# node.net
KiCad netlist of a schematic drawn in Altium Designer
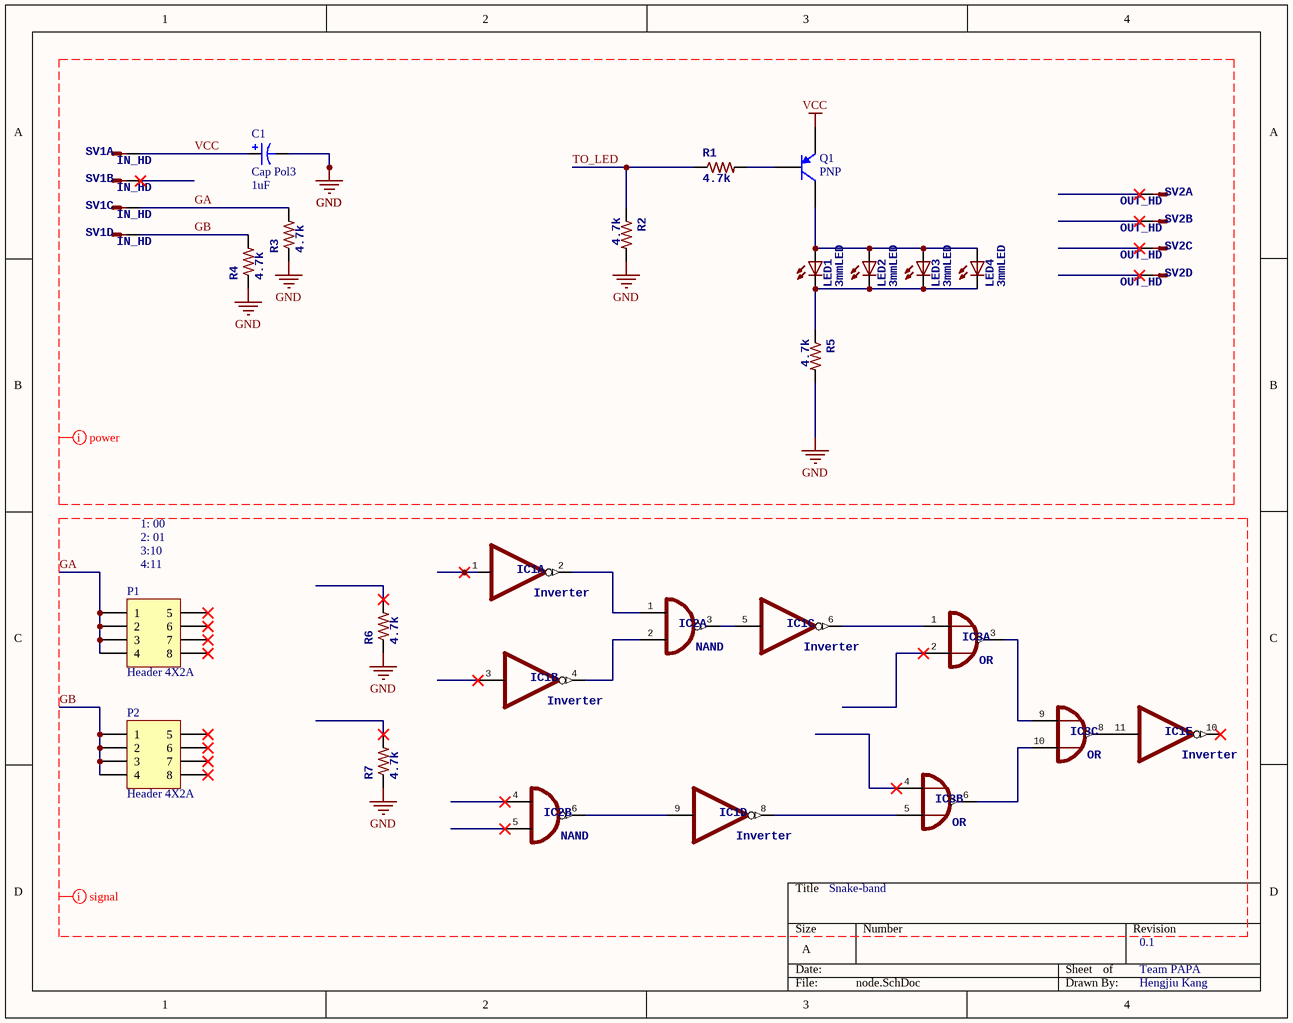
[diagram p0: node.SchDoc]

(export (version "E")
  (design (tool "Eeschema 10.0.6"))
  (components
    (comp (ref "C1")
      (value "Cap Pol3")
      (footprint "C0805")
      (description "Polarized Capacitor (Surface Mount)")
      (fields (field (name "ALTIUM_VALUE") "1uF") (field (name "PUBLISHER") "Altium Limited"))
      (libsource (lib "Miscellaneous Devices") (part "Cap Pol3"))
    )
    (comp (ref "IC1") (value "Inverter") (footprint "ssop14") (libsource (lib "74xx-eu") (part "74*04DB")))
    (comp (ref "IC2") (value "NAND") (footprint "SSOP14") (libsource (lib "74xx-eu") (part "74*00DB")))
    (comp (ref "IC3") (value "OR") (footprint "ssop14") (libsource (lib "74xx-eu") (part "74*32DB")))
    (comp (ref "LED1") (value "3mmLED") (footprint "LED3MM") (libsource (lib "adafruit") (part "LED3MM")))
    (comp (ref "LED2") (value "3mmLED") (footprint "LED3MM") (libsource (lib "adafruit") (part "LED3MM")))
    (comp (ref "LED3") (value "3mmLED") (footprint "LED3MM") (libsource (lib "adafruit") (part "LED3MM")))
    (comp (ref "LED4") (value "3mmLED") (footprint "LED3MM") (libsource (lib "adafruit") (part "LED3MM")))
    (comp (ref "P1")
      (value "Header 4X2A")
      (footprint "HDR2X4_CEN")
      (description "Header, 4-Pin, Dual row")
      (fields (field (name "PUBLISHER") "Altium Limited"))
      (libsource (lib "Miscellaneous Connectors") (part "Header 4X2A"))
    )
    (comp (ref "P2")
      (value "Header 4X2A")
      (footprint "HDR2X4_CEN")
      (description "Header, 4-Pin, Dual row")
      (fields (field (name "PUBLISHER") "Altium Limited"))
      (libsource (lib "Miscellaneous Connectors") (part "Header 4X2A"))
    )
    (comp (ref "Q1")
      (value "PNP")
      (footprint "SOT-23B_N")
      (description "PNP Bipolar Transistor")
      (fields (field (name "PUBLISHER") "Altium Limited"))
      (libsource (lib "Miscellaneous Devices") (part "PNP"))
    )
    (comp (ref "R1")
      (value "4.7k")
      (footprint "M0805")
      (description "R-M0805")
      (libsource (lib "adafruit") (part "R-US_M0805"))
    )
    (comp (ref "R2")
      (value "4.7k")
      (footprint "M0805")
      (description "R-M0805")
      (libsource (lib "adafruit") (part "R-US_M0805"))
    )
    (comp (ref "R3")
      (value "4.7k")
      (footprint "M0805")
      (description "R-M0805")
      (libsource (lib "adafruit") (part "R-US_M0805"))
    )
    (comp (ref "R4")
      (value "4.7k")
      (footprint "M0805")
      (description "R-M0805")
      (libsource (lib "adafruit") (part "R-US_M0805"))
    )
    (comp (ref "R5")
      (value "4.7k")
      (footprint "M0805")
      (description "R-M0805")
      (libsource (lib "adafruit") (part "R-US_M0805"))
    )
    (comp (ref "R6")
      (value "4.7k")
      (footprint "M0805")
      (description "R-M0805")
      (libsource (lib "adafruit") (part "R-US_M0805"))
    )
    (comp (ref "R7") (value "4.7k") (footprint "M0805") (libsource (lib "adafruit") (part "R-US_M0805")))
    (comp (ref "SV1") (value "IN_HD") (footprint "L04P") (libsource (lib "con-amp-mt") (part "L04P")))
    (comp (ref "SV2") (value "OUT_HD") (footprint "L04P") (libsource (lib "con-amp-mt") (part "L04P")))
  )
  (nets
    (net (code "1") (name "/GA") (class "Default")
      (node (ref "P1") (pin "1") (pinfunction "1_1") (pintype "passive"))
      (node (ref "P1") (pin "2") (pinfunction "2_2") (pintype "passive"))
      (node (ref "P1") (pin "3") (pinfunction "3_3") (pintype "passive"))
      (node (ref "P1") (pin "4") (pinfunction "4_4") (pintype "passive"))
      (node (ref "R3") (pin "2") (pinfunction "2_2") (pintype "passive"))
      (node (ref "SV1") (pin "3") (pinfunction "S_3") (pintype "passive"))
    )
    (net (code "2") (name "/GB") (class "Default")
      (node (ref "P2") (pin "1") (pinfunction "1_1") (pintype "passive"))
      (node (ref "P2") (pin "2") (pinfunction "2_2") (pintype "passive"))
      (node (ref "P2") (pin "3") (pinfunction "3_3") (pintype "passive"))
      (node (ref "P2") (pin "4") (pinfunction "4_4") (pintype "passive"))
      (node (ref "R4") (pin "2") (pinfunction "2_2") (pintype "passive"))
      (node (ref "SV1") (pin "4") (pinfunction "S_4") (pintype "passive"))
    )
    (net (code "3") (name "/TO_LED") (class "Default")
      (node (ref "R1") (pin "1") (pinfunction "1_1") (pintype "passive"))
      (node (ref "R2") (pin "1") (pinfunction "1_1") (pintype "passive"))
    )
    (net (code "4") (name "GND") (class "Default")
      (node (ref "C1") (pin "2") (pinfunction "2_2") (pintype "passive"))
      (node (ref "R2") (pin "2") (pinfunction "2_2") (pintype "passive"))
      (node (ref "R3") (pin "1") (pinfunction "1_1") (pintype "passive"))
      (node (ref "R4") (pin "1") (pinfunction "1_1") (pintype "passive"))
      (node (ref "R5") (pin "2") (pinfunction "2_2") (pintype "passive"))
      (node (ref "R6") (pin "1") (pinfunction "1_1") (pintype "passive"))
      (node (ref "R7") (pin "1") (pinfunction "1_1") (pintype "passive"))
    )
    (net (code "5") (name "Net-(IC1A-O)") (class "Default")
      (node (ref "IC1") (pin "2") (pinfunction "O_2") (pintype "output"))
      (node (ref "IC2") (pin "1") (pinfunction "I0_1") (pintype "passive"))
    )
    (net (code "6") (name "Net-(IC1B-O)") (class "Default")
      (node (ref "IC1") (pin "4") (pinfunction "O_4") (pintype "output"))
      (node (ref "IC2") (pin "2") (pinfunction "I1_2") (pintype "passive"))
    )
    (net (code "7") (name "Net-(IC1C-I)") (class "Default")
      (node (ref "IC1") (pin "5") (pinfunction "I_5") (pintype "passive"))
      (node (ref "IC2") (pin "3") (pinfunction "O_3") (pintype "output"))
    )
    (net (code "8") (name "Net-(IC1C-O)") (class "Default")
      (node (ref "IC1") (pin "6") (pinfunction "O_6") (pintype "output"))
      (node (ref "IC3") (pin "1") (pinfunction "I0_1") (pintype "passive"))
    )
    (net (code "9") (name "Net-(IC1D-I)") (class "Default")
      (node (ref "IC1") (pin "9") (pinfunction "I_9") (pintype "passive"))
      (node (ref "IC2") (pin "6") (pinfunction "O_6") (pintype "output"))
    )
    (net (code "10") (name "Net-(IC1D-O)") (class "Default")
      (node (ref "IC1") (pin "8") (pinfunction "O_8") (pintype "output"))
      (node (ref "IC3") (pin "5") (pinfunction "I1_5") (pintype "passive"))
    )
    (net (code "11") (name "Net-(IC1E-I)") (class "Default")
      (node (ref "IC1") (pin "11") (pinfunction "I_11") (pintype "passive"))
      (node (ref "IC3") (pin "8") (pinfunction "O_8") (pintype "output"))
    )
    (net (code "12") (name "Net-(IC3A-O)") (class "Default")
      (node (ref "IC3") (pin "3") (pinfunction "O_3") (pintype "output"))
      (node (ref "IC3") (pin "9") (pinfunction "I0_9") (pintype "passive"))
    )
    (net (code "13") (name "Net-(IC3B-O)") (class "Default")
      (node (ref "IC3") (pin "10") (pinfunction "I1_10") (pintype "passive"))
      (node (ref "IC3") (pin "6") (pinfunction "O_6") (pintype "output"))
    )
    (net (code "14") (name "Net-(LED1-C)") (class "Default")
      (node (ref "LED1") (pin "K") (pinfunction "C_K") (pintype "passive"))
      (node (ref "LED2") (pin "K") (pinfunction "C_K") (pintype "passive"))
      (node (ref "LED3") (pin "K") (pinfunction "C_K") (pintype "passive"))
      (node (ref "LED4") (pin "K") (pinfunction "C_K") (pintype "passive"))
      (node (ref "R5") (pin "1") (pinfunction "1_1") (pintype "passive"))
    )
    (net (code "15") (name "Net-(Q1-B)") (class "Default")
      (node (ref "Q1") (pin "2") (pinfunction "B_2") (pintype "passive"))
      (node (ref "R1") (pin "2") (pinfunction "2_2") (pintype "passive"))
    )
    (net (code "16") (name "Net-(Q1-C)") (class "Default")
      (node (ref "LED1") (pin "A") (pinfunction "A_A") (pintype "passive"))
      (node (ref "LED2") (pin "A") (pinfunction "A_A") (pintype "passive"))
      (node (ref "LED3") (pin "A") (pinfunction "A_A") (pintype "passive"))
      (node (ref "LED4") (pin "A") (pinfunction "A_A") (pintype "passive"))
      (node (ref "Q1") (pin "1") (pinfunction "C_1") (pintype "passive"))
    )
    (net (code "17") (name "VCC") (class "Default")
      (node (ref "C1") (pin "1") (pinfunction "1_1") (pintype "passive"))
      (node (ref "Q1") (pin "3") (pinfunction "E_3") (pintype "passive"))
      (node (ref "SV1") (pin "1") (pinfunction "S_1") (pintype "passive"))
    )
    (net (code "18") (name "unconnected-(IC1A-I-Pad1)") (class "Default")
      (node (ref "IC1") (pin "1") (pinfunction "I_1") (pintype "passive+no_connect"))
    )
    (net (code "19") (name "unconnected-(IC1B-I-Pad3)") (class "Default")
      (node (ref "IC1") (pin "3") (pinfunction "I_3") (pintype "passive+no_connect"))
    )
    (net (code "20") (name "unconnected-(IC1E-O-Pad10)") (class "Default")
      (node (ref "IC1") (pin "10") (pinfunction "O_10") (pintype "output+no_connect"))
    )
    (net (code "21") (name "unconnected-(IC2B-I0-Pad4)") (class "Default")
      (node (ref "IC2") (pin "4") (pinfunction "I0_4") (pintype "passive+no_connect"))
    )
    (net (code "22") (name "unconnected-(IC2B-I1-Pad5)") (class "Default")
      (node (ref "IC2") (pin "5") (pinfunction "I1_5") (pintype "passive+no_connect"))
    )
    (net (code "23") (name "unconnected-(IC3A-I1-Pad2)") (class "Default")
      (node (ref "IC3") (pin "2") (pinfunction "I1_2") (pintype "passive+no_connect"))
    )
    (net (code "24") (name "unconnected-(IC3B-I0-Pad4)") (class "Default")
      (node (ref "IC3") (pin "4") (pinfunction "I0_4") (pintype "passive+no_connect"))
    )
    (net (code "25") (name "unconnected-(P1-Pad5)") (class "Default")
      (node (ref "P1") (pin "5") (pinfunction "5_5") (pintype "passive+no_connect"))
    )
    (net (code "26") (name "unconnected-(P1-Pad6)") (class "Default")
      (node (ref "P1") (pin "6") (pinfunction "6_6") (pintype "passive+no_connect"))
    )
    (net (code "27") (name "unconnected-(P1-Pad7)") (class "Default")
      (node (ref "P1") (pin "7") (pinfunction "7_7") (pintype "passive+no_connect"))
    )
    (net (code "28") (name "unconnected-(P1-Pad8)") (class "Default")
      (node (ref "P1") (pin "8") (pinfunction "8_8") (pintype "passive+no_connect"))
    )
    (net (code "29") (name "unconnected-(P2-Pad5)") (class "Default")
      (node (ref "P2") (pin "5") (pinfunction "5_5") (pintype "passive+no_connect"))
    )
    (net (code "30") (name "unconnected-(P2-Pad6)") (class "Default")
      (node (ref "P2") (pin "6") (pinfunction "6_6") (pintype "passive+no_connect"))
    )
    (net (code "31") (name "unconnected-(P2-Pad7)") (class "Default")
      (node (ref "P2") (pin "7") (pinfunction "7_7") (pintype "passive+no_connect"))
    )
    (net (code "32") (name "unconnected-(P2-Pad8)") (class "Default")
      (node (ref "P2") (pin "8") (pinfunction "8_8") (pintype "passive+no_connect"))
    )
    (net (code "33") (name "unconnected-(R6-Pad2)") (class "Default")
      (node (ref "R6") (pin "2") (pinfunction "2_2") (pintype "passive+no_connect"))
    )
    (net (code "34") (name "unconnected-(R7-Pad2)") (class "Default")
      (node (ref "R7") (pin "2") (pinfunction "2_2") (pintype "passive+no_connect"))
    )
    (net (code "35") (name "unconnected-(SV1B-S-Pad2)") (class "Default")
      (node (ref "SV1") (pin "2") (pinfunction "S_2") (pintype "passive+no_connect"))
    )
    (net (code "36") (name "unconnected-(SV2A-S-Pad1)") (class "Default")
      (node (ref "SV2") (pin "1") (pinfunction "S_1") (pintype "passive+no_connect"))
    )
    (net (code "37") (name "unconnected-(SV2B-S-Pad2)") (class "Default")
      (node (ref "SV2") (pin "2") (pinfunction "S_2") (pintype "passive+no_connect"))
    )
    (net (code "38") (name "unconnected-(SV2C-S-Pad3)") (class "Default")
      (node (ref "SV2") (pin "3") (pinfunction "S_3") (pintype "passive+no_connect"))
    )
    (net (code "39") (name "unconnected-(SV2D-S-Pad4)") (class "Default")
      (node (ref "SV2") (pin "4") (pinfunction "S_4") (pintype "passive+no_connect"))
    )
  )
)
